# FPGA_MIO.net
KiCad netlist of a schematic drawn in Altium Designer
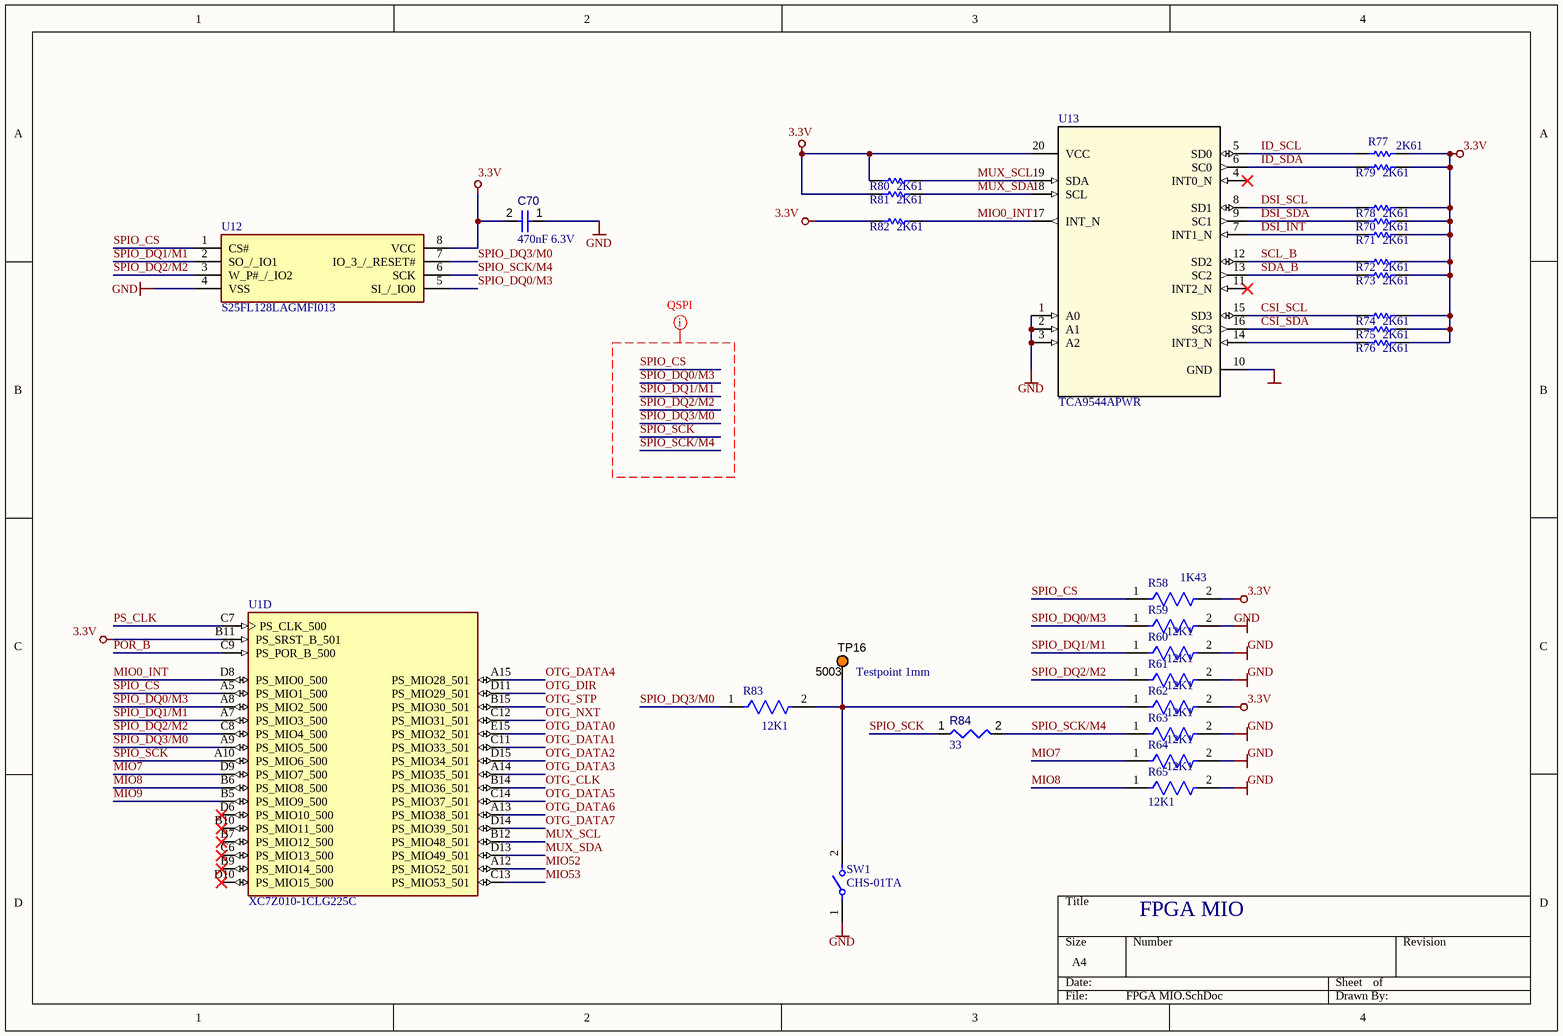
[diagram p0: FPGA MIO.SchDoc]

(export (version "E")
  (design (tool "Eeschema 10.0.6"))
  (components
    (comp (ref "C70")
      (value "470nF 6.3V")
      (footprint "CAPC0603(1608)100_L")
      (description "Chip Capacitor, 470nF +/-20%, 25V, 0603, Thickness 1 mm")
      (fields (field (name "TOLERANCE") "10%") (field (name "Comment") "Capacitor 470nF +/-20% 25V 0603"))
      (libsource (lib "Meenakshi Shyam") (part "CAP-NP-2"))
    )
    (comp (ref "R58")
      (value "1K43")
      (footprint "FP-RMCF1210-IPC_B")
      (description "1.43kΩ ±1% 0.5W 1210 Thick Film Chip Resistor AEC-Q200 compliant")
      (fields (field (name "TOLERANCE") "1%"))
      (libsource (lib "Altium Content Vault") (part "1029c3af85768c4190bb7ad29bc67b5"))
    )
    (comp (ref "R59")
      (value "12K1")
      (footprint "FP-RMCF0805-MFG")
      (description "12.1kΩ ±1% 0.125W 0805 Thick Film Chip Resistor AEC-Q200 compliant")
      (fields (field (name "TOLERANCE") "1%"))
      (libsource (lib "Altium Content Vault") (part "1029c3af85768c4190bb7ad29bc67b5"))
    )
    (comp (ref "R60")
      (value "12K1")
      (footprint "FP-RMCF0805-MFG")
      (description "12.1kΩ ±1% 0.125W 0805 Thick Film Chip Resistor AEC-Q200 compliant")
      (fields (field (name "TOLERANCE") "1%"))
      (libsource (lib "Altium Content Vault") (part "1029c3af85768c4190bb7ad29bc67b5"))
    )
    (comp (ref "R61")
      (value "12K1")
      (footprint "FP-RMCF0805-MFG")
      (description "12.1kΩ ±1% 0.125W 0805 Thick Film Chip Resistor AEC-Q200 compliant")
      (fields (field (name "TOLERANCE") "1%"))
      (libsource (lib "Altium Content Vault") (part "1029c3af85768c4190bb7ad29bc67b5"))
    )
    (comp (ref "R62")
      (value "12K1")
      (footprint "FP-RMCF0805-MFG")
      (description "12.1kΩ ±1% 0.125W 0805 Thick Film Chip Resistor AEC-Q200 compliant")
      (fields (field (name "TOLERANCE") "1%"))
      (libsource (lib "Altium Content Vault") (part "1029c3af85768c4190bb7ad29bc67b5"))
    )
    (comp (ref "R63")
      (value "12K1")
      (footprint "FP-RMCF0805-MFG")
      (description "12.1kΩ ±1% 0.125W 0805 Thick Film Chip Resistor AEC-Q200 compliant")
      (fields (field (name "TOLERANCE") "1%"))
      (libsource (lib "Altium Content Vault") (part "1029c3af85768c4190bb7ad29bc67b5"))
    )
    (comp (ref "R64")
      (value "12K1")
      (footprint "FP-RMCF0805-MFG")
      (description "12.1kΩ ±1% 0.125W 0805 Thick Film Chip Resistor AEC-Q200 compliant")
      (fields (field (name "TOLERANCE") "1%"))
      (libsource (lib "Altium Content Vault") (part "1029c3af85768c4190bb7ad29bc67b5"))
    )
    (comp (ref "R65")
      (value "12K1")
      (footprint "FP-RMCF0805-MFG")
      (description "12.1kΩ ±1% 0.125W 0805 Thick Film Chip Resistor AEC-Q200 compliant")
      (fields (field (name "TOLERANCE") "1%"))
      (libsource (lib "Altium Content Vault") (part "1029c3af85768c4190bb7ad29bc67b5"))
    )
    (comp (ref "R70")
      (value "2K61")
      (footprint "RESC1812(4532)_N")
      (description "2K61 0.75W 1% 1812 (4532 Metric)  SMD")
      (fields (field (name "POWER") "0.75 W") (field (name "TOLERANCE") "1 %"))
      (libsource (lib "Altium Content Vault") (part "RES"))
    )
    (comp (ref "R71")
      (value "2K61")
      (footprint "RESC1812(4532)_N")
      (description "2K61 0.75W 1% 1812 (4532 Metric)  SMD")
      (fields (field (name "POWER") "0.75 W") (field (name "TOLERANCE") "1 %"))
      (libsource (lib "Altium Content Vault") (part "RES"))
    )
    (comp (ref "R72")
      (value "2K61")
      (footprint "RESC1812(4532)_N")
      (description "2K61 0.75W 1% 1812 (4532 Metric)  SMD")
      (fields (field (name "POWER") "0.75 W") (field (name "TOLERANCE") "1 %"))
      (libsource (lib "Altium Content Vault") (part "RES"))
    )
    (comp (ref "R73")
      (value "2K61")
      (footprint "RESC1812(4532)_N")
      (description "2K61 0.75W 1% 1812 (4532 Metric)  SMD")
      (fields (field (name "POWER") "0.75 W") (field (name "TOLERANCE") "1 %"))
      (libsource (lib "Altium Content Vault") (part "RES"))
    )
    (comp (ref "R74")
      (value "2K61")
      (footprint "RESC1812(4532)_N")
      (description "2K61 0.75W 1% 1812 (4532 Metric)  SMD")
      (fields (field (name "POWER") "0.75 W") (field (name "TOLERANCE") "1 %"))
      (libsource (lib "Altium Content Vault") (part "RES"))
    )
    (comp (ref "R75")
      (value "2K61")
      (footprint "RESC1812(4532)_N")
      (description "2K61 0.75W 1% 1812 (4532 Metric)  SMD")
      (fields (field (name "POWER") "0.75 W") (field (name "TOLERANCE") "1 %"))
      (libsource (lib "Altium Content Vault") (part "RES"))
    )
    (comp (ref "R76")
      (value "2K61")
      (footprint "RESC1812(4532)_N")
      (description "2K61 0.75W 1% 1812 (4532 Metric)  SMD")
      (fields (field (name "POWER") "0.75 W") (field (name "TOLERANCE") "1 %"))
      (libsource (lib "Altium Content Vault") (part "RES"))
    )
    (comp (ref "R77")
      (value "2K61")
      (footprint "RESC1812(4532)_N")
      (description "2K61 0.75W 1% 1812 (4532 Metric)  SMD")
      (fields (field (name "POWER") "0.75 W") (field (name "TOLERANCE") "1 %"))
      (libsource (lib "Altium Content Vault") (part "RES"))
    )
    (comp (ref "R78")
      (value "2K61")
      (footprint "RESC1812(4532)_N")
      (description "2K61 0.75W 1% 1812 (4532 Metric)  SMD")
      (fields (field (name "POWER") "0.75 W") (field (name "TOLERANCE") "1 %"))
      (libsource (lib "Altium Content Vault") (part "RES"))
    )
    (comp (ref "R79")
      (value "2K61")
      (footprint "RESC1812(4532)_N")
      (description "2K61 0.75W 1% 1812 (4532 Metric)  SMD")
      (fields (field (name "POWER") "0.75 W") (field (name "TOLERANCE") "1 %"))
      (libsource (lib "Altium Content Vault") (part "RES"))
    )
    (comp (ref "R80")
      (value "2K61")
      (footprint "RESC1812(4532)_N")
      (description "2K61 0.75W 1% 1812 (4532 Metric)  SMD")
      (fields (field (name "POWER") "0.75 W") (field (name "TOLERANCE") "1 %"))
      (libsource (lib "Altium Content Vault") (part "RES"))
    )
    (comp (ref "R81")
      (value "2K61")
      (footprint "RESC1812(4532)_N")
      (description "2K61 0.75W 1% 1812 (4532 Metric)  SMD")
      (fields (field (name "POWER") "0.75 W") (field (name "TOLERANCE") "1 %"))
      (libsource (lib "Altium Content Vault") (part "RES"))
    )
    (comp (ref "R82")
      (value "2K61")
      (footprint "RESC1812(4532)_N")
      (description "2K61 0.75W 1% 1812 (4532 Metric)  SMD")
      (fields (field (name "POWER") "0.75 W") (field (name "TOLERANCE") "1 %"))
      (libsource (lib "Altium Content Vault") (part "RES"))
    )
    (comp (ref "R83")
      (value "12K1")
      (footprint "FP-RMCF0805-MFG")
      (description "12.1kΩ ±1% 0.125W 0805 Thick Film Chip Resistor AEC-Q200 compliant")
      (fields (field (name "TOLERANCE") "1%"))
      (libsource (lib "Altium Content Vault") (part "1029c3af85768c4190bb7ad29bc67b5"))
    )
    (comp (ref "R84")
      (value "33")
      (footprint "RESC1005X40X25ML10T10")
      (description "Chip Resistor, 33 Ohm, +/- 1%, 0.063 W, -55 to 155 degC, 0402 (1005 Metric)")
      (fields (field (name "POWER") "63mW") (field (name "TOLERANCE") "1%"))
      (libsource (lib "Meenakshi Shyam") (part "RES-2"))
    )
    (comp (ref "SW1")
      (value "CHS-01TA")
      (footprint "FP-CHS-01TA-MFG")
      (description "SWITCH SLIDE DIP SPST 100MA 6V")
      (fields
        (field (name "OCTOPART") "https://octopart.com/chs-01ta-nidec+copal-52304644")
        (field (name "MANUFACTURER") "Nidec Copal Electronics")
      )
      (libsource (lib "Altium Content Vault") (part "bb27bde45df87f1f469753f287ef5ae"))
    )
    (comp (ref "TP16")
      (value "5003")
      (footprint "KSTN-5003")
      (description "Test Point, Orange, Height 4.6 mm, Tail Length 3 mm, 1-Pin THD, RoHS")
      (fields (field (name "MANUFACTURER") "Keystone"))
      (libsource (lib "Meenakshi Shyam") (part "TESTPOINT_ORANGE"))
    )
    (comp (ref "U1")
      (value "XC7Z010-1CLG225C")
      (footprint "BGA225C80P15X15_1300X1300X150")
      (fields (field (name "DIGI-KEY_PART_NUMBER") "122-1855-ND") (field (name "MF") "Xilinx Inc."))
      (libsource (lib "Meenakshi Shyam") (part "XC7Z010-1CLG225C"))
    )
    (comp (ref "U12")
      (value "S25FL128LAGMFI013")
      (footprint "SamacSys:SOIC127P800X216-8N")
      (description "Integrated Circuit")
      (fields (field (name "MOUSER PART NUMBER") "727-S25FL128LAGMF013"))
      (libsource (lib "*") (part "S25FL128LAGMFI013"))
    )
    (comp (ref "U13")
      (value "TCA9544APWR")
      (footprint "PW0020A_N")
      (fields
        (field (name "MANUFACTURER") "Texas Instruments")
        (field (name "COPYRIGHT") "Copyright (C) 2025 Ultra Librarian. All rights reserved.")
      )
      (libsource (lib "Meenakshi Shyam") (part "TCA9544APWR"))
    )
  )
  (nets
    (net (code "2") (name "/CSI_SCL") (class "Default")
      (node (ref "R74") (pin "1") (pinfunction "1_1") (pintype "passive"))
      (node (ref "U13") (pin "15") (pinfunction "SD3_15") (pintype "bidirectional"))
    )
    (net (code "3") (name "/CSI_SDA") (class "Default")
      (node (ref "R75") (pin "1") (pinfunction "1_1") (pintype "passive"))
      (node (ref "U13") (pin "16") (pinfunction "SC3_16") (pintype "output"))
    )
    (net (code "4") (name "/DSI_INT") (class "Default")
      (node (ref "R71") (pin "1") (pinfunction "1_1") (pintype "passive"))
      (node (ref "U13") (pin "7") (pinfunction "INT1_N_7") (pintype "input"))
    )
    (net (code "5") (name "/DSI_SCL") (class "Default")
      (node (ref "R78") (pin "1") (pinfunction "1_1") (pintype "passive"))
      (node (ref "U13") (pin "8") (pinfunction "SD1_8") (pintype "bidirectional"))
    )
    (net (code "6") (name "/DSI_SDA") (class "Default")
      (node (ref "R70") (pin "1") (pinfunction "1_1") (pintype "passive"))
      (node (ref "U13") (pin "9") (pinfunction "SC1_9") (pintype "output"))
    )
    (net (code "7") (name "/ID_SCL") (class "Default")
      (node (ref "R77") (pin "1") (pinfunction "1_1") (pintype "passive"))
      (node (ref "U13") (pin "5") (pinfunction "SD0_5") (pintype "bidirectional"))
    )
    (net (code "8") (name "/ID_SDA") (class "Default")
      (node (ref "R79") (pin "1") (pinfunction "1_1") (pintype "passive"))
      (node (ref "U13") (pin "6") (pinfunction "SC0_6") (pintype "output"))
    )
    (net (code "9") (name "/MIO0_INT") (class "Default")
      (node (ref "R82") (pin "2") (pinfunction "2_2") (pintype "passive"))
      (node (ref "U1") (pin "D8") (pinfunction "PS_MIO0_500_D8") (pintype "bidirectional"))
      (node (ref "U13") (pin "17") (pinfunction "INT_N_17") (pintype "output"))
    )
    (net (code "10") (name "/MIO7") (class "Default")
      (node (ref "R64") (pin "1") (pinfunction "1_1") (pintype "passive"))
      (node (ref "U1") (pin "D9") (pinfunction "PS_MIO7_500_D9") (pintype "bidirectional"))
    )
    (net (code "11") (name "/MIO8") (class "Default")
      (node (ref "R65") (pin "1") (pinfunction "1_1") (pintype "passive"))
      (node (ref "U1") (pin "B6") (pinfunction "PS_MIO8_500_B6") (pintype "bidirectional"))
    )
    (net (code "12") (name "/MIO9") (class "Default")
      (node (ref "U1") (pin "B5") (pinfunction "PS_MIO9_500_B5") (pintype "bidirectional"))
    )
    (net (code "13") (name "/MIO52") (class "Default")
      (node (ref "U1") (pin "A12") (pinfunction "PS_MIO52_501_A12") (pintype "bidirectional"))
    )
    (net (code "14") (name "/MIO53") (class "Default")
      (node (ref "U1") (pin "C13") (pinfunction "PS_MIO53_501_C13") (pintype "bidirectional"))
    )
    (net (code "15") (name "/MUX_SCL") (class "Default")
      (node (ref "R80") (pin "2") (pinfunction "2_2") (pintype "passive"))
      (node (ref "U1") (pin "B12") (pinfunction "PS_MIO48_501_B12") (pintype "bidirectional"))
      (node (ref "U13") (pin "19") (pinfunction "SDA_19") (pintype "input"))
    )
    (net (code "16") (name "/MUX_SDA") (class "Default")
      (node (ref "R81") (pin "2") (pinfunction "2_2") (pintype "passive"))
      (node (ref "U1") (pin "D13") (pinfunction "PS_MIO49_501_D13") (pintype "bidirectional"))
      (node (ref "U13") (pin "18") (pinfunction "SCL_18") (pintype "input"))
    )
    (net (code "17") (name "/OTG_CLK") (class "Default")
      (node (ref "U1") (pin "B14") (pinfunction "PS_MIO36_501_B14") (pintype "bidirectional"))
    )
    (net (code "18") (name "/OTG_DATA0") (class "Default")
      (node (ref "U1") (pin "E15") (pinfunction "PS_MIO32_501_E15") (pintype "bidirectional"))
    )
    (net (code "19") (name "/OTG_DATA1") (class "Default")
      (node (ref "U1") (pin "C11") (pinfunction "PS_MIO33_501_C11") (pintype "bidirectional"))
    )
    (net (code "20") (name "/OTG_DATA2") (class "Default")
      (node (ref "U1") (pin "D15") (pinfunction "PS_MIO34_501_D15") (pintype "bidirectional"))
    )
    (net (code "21") (name "/OTG_DATA3") (class "Default")
      (node (ref "U1") (pin "A14") (pinfunction "PS_MIO35_501_A14") (pintype "bidirectional"))
    )
    (net (code "22") (name "/OTG_DATA4") (class "Default")
      (node (ref "U1") (pin "A15") (pinfunction "PS_MIO28_501_A15") (pintype "bidirectional"))
    )
    (net (code "23") (name "/OTG_DATA5") (class "Default")
      (node (ref "U1") (pin "C14") (pinfunction "PS_MIO37_501_C14") (pintype "bidirectional"))
    )
    (net (code "24") (name "/OTG_DATA6") (class "Default")
      (node (ref "U1") (pin "A13") (pinfunction "PS_MIO38_501_A13") (pintype "bidirectional"))
    )
    (net (code "25") (name "/OTG_DATA7") (class "Default")
      (node (ref "U1") (pin "D14") (pinfunction "PS_MIO39_501_D14") (pintype "bidirectional"))
    )
    (net (code "26") (name "/OTG_DIR") (class "Default")
      (node (ref "U1") (pin "D11") (pinfunction "PS_MIO29_501_D11") (pintype "bidirectional"))
    )
    (net (code "27") (name "/OTG_NXT") (class "Default")
      (node (ref "U1") (pin "C12") (pinfunction "PS_MIO31_501_C12") (pintype "bidirectional"))
    )
    (net (code "28") (name "/OTG_STP") (class "Default")
      (node (ref "U1") (pin "B15") (pinfunction "PS_MIO30_501_B15") (pintype "bidirectional"))
    )
    (net (code "29") (name "/POR_B") (class "Default")
      (node (ref "U1") (pin "C9") (pinfunction "PS_POR_B_500_C9") (pintype "input"))
    )
    (net (code "30") (name "/PS_CLK") (class "Default")
      (node (ref "U1") (pin "C7") (pinfunction "PS_CLK_500_C7") (pintype "input"))
    )
    (net (code "31") (name "/SCL_B") (class "Default")
      (node (ref "R72") (pin "1") (pinfunction "1_1") (pintype "passive"))
      (node (ref "U13") (pin "12") (pinfunction "SD2_12") (pintype "bidirectional"))
    )
    (net (code "32") (name "/SDA_B") (class "Default")
      (node (ref "R73") (pin "1") (pinfunction "1_1") (pintype "passive"))
      (node (ref "U13") (pin "13") (pinfunction "SC2_13") (pintype "output"))
    )
    (net (code "33") (name "/SPIO_CS") (class "Default")
      (node (ref "R58") (pin "1") (pinfunction "1_1") (pintype "passive"))
      (node (ref "U1") (pin "A5") (pinfunction "PS_MIO1_500_A5") (pintype "bidirectional"))
      (node (ref "U12") (pin "1") (pinfunction "CS#_1") (pintype "passive"))
    )
    (net (code "34") (name "/SPIO_DQ0{slash}M3") (class "Default")
      (node (ref "R59") (pin "1") (pinfunction "1_1") (pintype "passive"))
      (node (ref "U1") (pin "A8") (pinfunction "PS_MIO2_500_A8") (pintype "bidirectional"))
      (node (ref "U12") (pin "5") (pinfunction "SI_/_IO0_5") (pintype "passive"))
    )
    (net (code "35") (name "/SPIO_DQ1{slash}M1") (class "Default")
      (node (ref "R60") (pin "1") (pinfunction "1_1") (pintype "passive"))
      (node (ref "U1") (pin "A7") (pinfunction "PS_MIO3_500_A7") (pintype "bidirectional"))
      (node (ref "U12") (pin "2") (pinfunction "SO_/_IO1_2") (pintype "passive"))
    )
    (net (code "36") (name "/SPIO_DQ2{slash}M2") (class "Default")
      (node (ref "R61") (pin "1") (pinfunction "1_1") (pintype "passive"))
      (node (ref "U1") (pin "C8") (pinfunction "PS_MIO4_500_C8") (pintype "bidirectional"))
      (node (ref "U12") (pin "3") (pinfunction "W_P#_/_IO2_3") (pintype "passive"))
    )
    (net (code "37") (name "/SPIO_DQ3{slash}M0") (class "Default")
      (node (ref "R83") (pin "1") (pinfunction "1_1") (pintype "passive"))
      (node (ref "U1") (pin "A9") (pinfunction "PS_MIO5_500_A9") (pintype "bidirectional"))
      (node (ref "U12") (pin "7") (pinfunction "IO_3_/_RESET#_7") (pintype "passive"))
    )
    (net (code "38") (name "/SPIO_SCK") (class "Default")
      (node (ref "R84") (pin "1") (pinfunction "1_1") (pintype "passive"))
      (node (ref "U1") (pin "A10") (pinfunction "PS_MIO6_500_A10") (pintype "bidirectional"))
    )
    (net (code "39") (name "/SPIO_SCK{slash}M4") (class "Default")
      (node (ref "R63") (pin "1") (pinfunction "1_1") (pintype "passive"))
      (node (ref "R84") (pin "2") (pinfunction "2_2") (pintype "passive"))
      (node (ref "U12") (pin "6") (pinfunction "SCK_6") (pintype "passive"))
    )
    (net (code "40") (name "GND") (class "Default")
      (node (ref "C70") (pin "1") (pinfunction "1_1") (pintype "passive"))
      (node (ref "C70") (pin "2") (pinfunction "2_2") (pintype "passive"))
      (node (ref "R58") (pin "2") (pinfunction "2_2") (pintype "passive"))
      (node (ref "R59") (pin "2") (pinfunction "2_2") (pintype "passive"))
      (node (ref "R60") (pin "2") (pinfunction "2_2") (pintype "passive"))
      (node (ref "R61") (pin "2") (pinfunction "2_2") (pintype "passive"))
      (node (ref "R62") (pin "2") (pinfunction "2_2") (pintype "passive"))
      (node (ref "R63") (pin "2") (pinfunction "2_2") (pintype "passive"))
      (node (ref "R64") (pin "2") (pinfunction "2_2") (pintype "passive"))
      (node (ref "R65") (pin "2") (pinfunction "2_2") (pintype "passive"))
      (node (ref "R70") (pin "2") (pinfunction "2_2") (pintype "passive"))
      (node (ref "R71") (pin "2") (pinfunction "2_2") (pintype "passive"))
      (node (ref "R72") (pin "2") (pinfunction "2_2") (pintype "passive"))
      (node (ref "R73") (pin "2") (pinfunction "2_2") (pintype "passive"))
      (node (ref "R74") (pin "2") (pinfunction "2_2") (pintype "passive"))
      (node (ref "R75") (pin "2") (pinfunction "2_2") (pintype "passive"))
      (node (ref "R76") (pin "2") (pinfunction "2_2") (pintype "passive"))
      (node (ref "R77") (pin "2") (pinfunction "2_2") (pintype "passive"))
      (node (ref "R78") (pin "2") (pinfunction "2_2") (pintype "passive"))
      (node (ref "R79") (pin "2") (pinfunction "2_2") (pintype "passive"))
      (node (ref "R80") (pin "1") (pinfunction "1_1") (pintype "passive"))
      (node (ref "R81") (pin "1") (pinfunction "1_1") (pintype "passive"))
      (node (ref "R82") (pin "1") (pinfunction "1_1") (pintype "passive"))
      (node (ref "SW1") (pin "1") (pinfunction "1_1") (pintype "passive"))
      (node (ref "U1") (pin "B11") (pinfunction "PS_SRST_B_501_B11") (pintype "input"))
      (node (ref "U12") (pin "4") (pinfunction "VSS_4") (pintype "passive"))
      (node (ref "U12") (pin "8") (pinfunction "VCC_8") (pintype "passive"))
      (node (ref "U13") (pin "1") (pinfunction "A0_1") (pintype "input"))
      (node (ref "U13") (pin "10") (pinfunction "GND_10") (pintype "power_in"))
      (node (ref "U13") (pin "2") (pinfunction "A1_2") (pintype "input"))
      (node (ref "U13") (pin "20") (pinfunction "VCC_20") (pintype "power_in"))
      (node (ref "U13") (pin "3") (pinfunction "A2_3") (pintype "input"))
    )
    (net (code "41") (name "Net-(R62-Pad1)") (class "Default")
      (node (ref "R62") (pin "1") (pinfunction "1_1") (pintype "passive"))
      (node (ref "R83") (pin "2") (pinfunction "2_2") (pintype "passive"))
      (node (ref "SW1") (pin "2") (pinfunction "2_2") (pintype "passive"))
      (node (ref "TP16") (pin "1") (pinfunction "1_1") (pintype "passive"))
    )
    (net (code "42") (name "Net-(U13-INT3_N)") (class "Default")
      (node (ref "R76") (pin "1") (pinfunction "1_1") (pintype "passive"))
      (node (ref "U13") (pin "14") (pinfunction "INT3_N_14") (pintype "input"))
    )
    (net (code "43") (name "unconnected-(U1D-PS_MIO10_500-PadD6)") (class "Default")
      (node (ref "U1") (pin "D6") (pinfunction "PS_MIO10_500_D6") (pintype "bidirectional+no_connect"))
    )
    (net (code "44") (name "unconnected-(U1D-PS_MIO11_500-PadB10)") (class "Default")
      (node (ref "U1") (pin "B10") (pinfunction "PS_MIO11_500_B10") (pintype "bidirectional+no_connect"))
    )
    (net (code "45") (name "unconnected-(U1D-PS_MIO12_500-PadB7)") (class "Default")
      (node (ref "U1") (pin "B7") (pinfunction "PS_MIO12_500_B7") (pintype "bidirectional+no_connect"))
    )
    (net (code "46") (name "unconnected-(U1D-PS_MIO13_500-PadC6)") (class "Default")
      (node (ref "U1") (pin "C6") (pinfunction "PS_MIO13_500_C6") (pintype "bidirectional+no_connect"))
    )
    (net (code "47") (name "unconnected-(U1D-PS_MIO14_500-PadB9)") (class "Default")
      (node (ref "U1") (pin "B9") (pinfunction "PS_MIO14_500_B9") (pintype "bidirectional+no_connect"))
    )
    (net (code "48") (name "unconnected-(U1D-PS_MIO15_500-PadD10)") (class "Default")
      (node (ref "U1") (pin "D10") (pinfunction "PS_MIO15_500_D10") (pintype "bidirectional+no_connect"))
    )
    (net (code "49") (name "unconnected-(U13-INT0_N-Pad4)") (class "Default")
      (node (ref "U13") (pin "4") (pinfunction "INT0_N_4") (pintype "input+no_connect"))
    )
    (net (code "50") (name "unconnected-(U13-INT2_N-Pad11)") (class "Default")
      (node (ref "U13") (pin "11") (pinfunction "INT2_N_11") (pintype "input+no_connect"))
    )
  )
)
